# Enregistreur_et_Speaker_Audio.net
KiCad netlist of a schematic drawn in Altium Designer
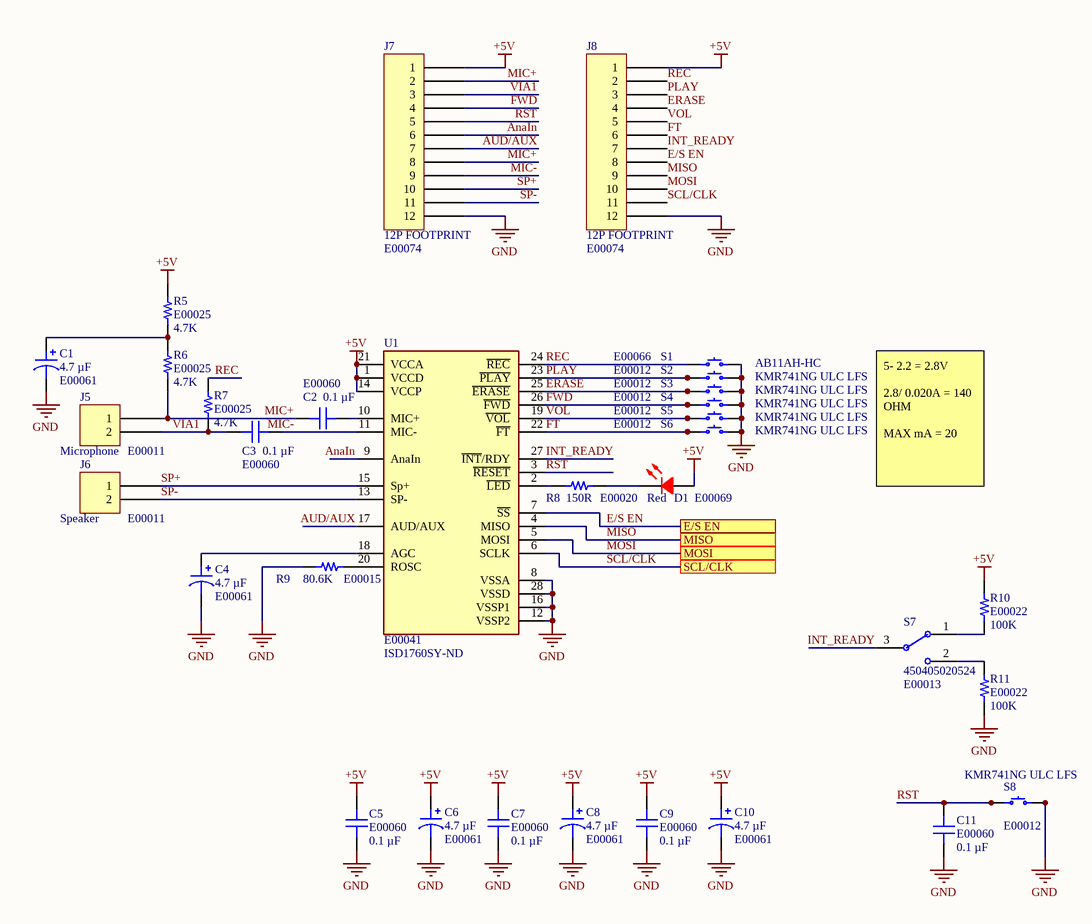
[diagram p0: Enregistreur et Speaker Audio.SchDoc]

(export (version "E")
  (design (tool "Eeschema 10.0.6"))
  (components
    (comp (ref "C1")
      (value "4.7 µF")
      (footprint "CAP ALUM 4.3MM2")
      (description "CAP ALUM 4.7UF 20% 35V SMD")
      (fields
        (field (name "MANUFACTURER") "United Chemi-Con")
        (field (name "TOLERANCE") "±20%")
        (field (name "ADAM INVENTORY NUMBER 1") "E00061")
      )
      (libsource (lib "ADAM LIBRARY") (part "CAP ALUM 4.7UF 20% 35V"))
    )
    (comp (ref "C2")
      (value "0.1 µF")
      (footprint "CAP 0603")
      (description "CAP CER 0.1UF 50V X7R 0603")
      (fields
        (field (name "MANUFACTURER") "KEMET")
        (field (name "TOLERANCE") "±10%")
        (field (name "ADAM INVENTORY NUMBER 1") "E00060")
      )
      (libsource (lib "ADAM LIBRARY") (part "CAP CER 0.1UF 50V X7R 0603"))
    )
    (comp (ref "C3")
      (value "0.1 µF")
      (footprint "CAP 0603")
      (description "CAP CER 0.1UF 50V X7R 0603")
      (fields
        (field (name "MANUFACTURER") "KEMET")
        (field (name "TOLERANCE") "±10%")
        (field (name "ADAM INVENTORY NUMBER 1") "E00060")
      )
      (libsource (lib "ADAM LIBRARY") (part "CAP CER 0.1UF 50V X7R 0603"))
    )
    (comp (ref "C4")
      (value "4.7 µF")
      (footprint "CAP ALUM 4.3MM2")
      (description "CAP ALUM 4.7UF 20% 35V SMD")
      (fields
        (field (name "MANUFACTURER") "United Chemi-Con")
        (field (name "TOLERANCE") "±20%")
        (field (name "ADAM INVENTORY NUMBER 1") "E00061")
      )
      (libsource (lib "ADAM LIBRARY") (part "CAP ALUM 4.7UF 20% 35V"))
    )
    (comp (ref "C5")
      (value "0.1 µF")
      (footprint "CAP 0603")
      (description "CAP CER 0.1UF 50V X7R 0603")
      (fields
        (field (name "MANUFACTURER") "KEMET")
        (field (name "TOLERANCE") "±10%")
        (field (name "ADAM INVENTORY NUMBER 1") "E00060")
      )
      (libsource (lib "ADAM LIBRARY") (part "CAP CER 0.1UF 50V X7R 0603"))
    )
    (comp (ref "C6")
      (value "4.7 µF")
      (footprint "CAP ALUM 4.3MM2")
      (description "CAP ALUM 4.7UF 20% 35V SMD")
      (fields
        (field (name "MANUFACTURER") "United Chemi-Con")
        (field (name "TOLERANCE") "±20%")
        (field (name "ADAM INVENTORY NUMBER 1") "E00061")
      )
      (libsource (lib "ADAM LIBRARY") (part "CAP ALUM 4.7UF 20% 35V"))
    )
    (comp (ref "C7")
      (value "0.1 µF")
      (footprint "CAP 0603")
      (description "CAP CER 0.1UF 50V X7R 0603")
      (fields
        (field (name "MANUFACTURER") "KEMET")
        (field (name "TOLERANCE") "±10%")
        (field (name "ADAM INVENTORY NUMBER 1") "E00060")
      )
      (libsource (lib "ADAM LIBRARY") (part "CAP CER 0.1UF 50V X7R 0603"))
    )
    (comp (ref "C8")
      (value "4.7 µF")
      (footprint "CAP ALUM 4.3MM2")
      (description "CAP ALUM 4.7UF 20% 35V SMD")
      (fields
        (field (name "MANUFACTURER") "United Chemi-Con")
        (field (name "TOLERANCE") "±20%")
        (field (name "ADAM INVENTORY NUMBER 1") "E00061")
      )
      (libsource (lib "ADAM LIBRARY") (part "CAP ALUM 4.7UF 20% 35V"))
    )
    (comp (ref "C9")
      (value "0.1 µF")
      (footprint "CAP 0603")
      (description "CAP CER 0.1UF 50V X7R 0603")
      (fields
        (field (name "MANUFACTURER") "KEMET")
        (field (name "TOLERANCE") "±10%")
        (field (name "ADAM INVENTORY NUMBER 1") "E00060")
      )
      (libsource (lib "ADAM LIBRARY") (part "CAP CER 0.1UF 50V X7R 0603"))
    )
    (comp (ref "C10")
      (value "4.7 µF")
      (footprint "CAP ALUM 4.3MM2")
      (description "CAP ALUM 4.7UF 20% 35V SMD")
      (fields
        (field (name "MANUFACTURER") "United Chemi-Con")
        (field (name "TOLERANCE") "±20%")
        (field (name "ADAM INVENTORY NUMBER 1") "E00061")
      )
      (libsource (lib "ADAM LIBRARY") (part "CAP ALUM 4.7UF 20% 35V"))
    )
    (comp (ref "C11")
      (value "0.1 µF")
      (footprint "CAP 0603")
      (description "CAP CER 0.1UF 50V X7R 0603")
      (fields
        (field (name "MANUFACTURER") "KEMET")
        (field (name "TOLERANCE") "±10%")
        (field (name "ADAM INVENTORY NUMBER 1") "E00060")
      )
      (libsource (lib "ADAM LIBRARY") (part "CAP CER 0.1UF 50V X7R 0603"))
    )
    (comp (ref "D1")
      (value "Red")
      (footprint "Red Led 0603")
      (description "0603 RED LED")
      (fields
        (field (name "MANUFACTURER") "American Bright Optoelectronics Corporation")
        (field (name "ADAM INVENTORY NUMBER 1") "E00069")
      )
      (libsource (lib "ADAM LIBRARY") (part "0603 RED LED"))
    )
    (comp (ref "J5")
      (value "Microphone")
      (footprint "TERM BLOC 2P")
      (description "TERM BLK 2P SIDE ENT 2.54MM PCB")
      (fields
        (field (name "MANUFACTURER") "TE Connectivity AMP Connectors")
        (field (name "VOLTAGE") "150V")
        (field (name "ADAM INVENTORY NUMBER 1") "E00011")
      )
      (libsource (lib "ADAM LIBRARY") (part "TERM BLK 2P SIDE ENT 2.54MM PCB"))
    )
    (comp (ref "J6")
      (value "Speaker")
      (footprint "TERM BLOC 2P")
      (description "TERM BLK 2P SIDE ENT 2.54MM PCB")
      (fields
        (field (name "MANUFACTURER") "TE Connectivity AMP Connectors")
        (field (name "VOLTAGE") "150V")
        (field (name "ADAM INVENTORY NUMBER 1") "E00011")
      )
      (libsource (lib "ADAM LIBRARY") (part "TERM BLK 2P SIDE ENT 2.54MM PCB"))
    )
    (comp (ref "J7")
      (value "12P FOOTPRINT")
      (footprint "CONN 12PIN FEMALE")
      (description "FOOTPRINT FOR TEST OR JUST IN CASE")
      (fields (field (name "MANUFACTURER") "Harwin Inc.") (field (name "ADAM INVENTORY NUMBER 1") "E00074"))
      (libsource (lib "ADAM LIBRARY") (part "12P FOOTPRINT"))
    )
    (comp (ref "J8")
      (value "12P FOOTPRINT")
      (footprint "CONN 12PIN FEMALE")
      (description "FOOTPRINT FOR TEST OR JUST IN CASE")
      (fields (field (name "MANUFACTURER") "Harwin Inc.") (field (name "ADAM INVENTORY NUMBER 1") "E00074"))
      (libsource (lib "ADAM LIBRARY") (part "12P FOOTPRINT"))
    )
    (comp (ref "R5")
      (value "4.7K")
      (footprint "RES 0603")
      (description "RES 4.7K OHM 1% 1/10W 0603")
      (fields
        (field (name "MANUFACTURER") "Stackpole Electronics Inc")
        (field (name "TOLERANCE") "±1%")
        (field (name "ADAM INVENTORY NUMBER 1") "E00025")
      )
      (libsource (lib "ADAM LIBRARY") (part "RES SMD 4.7K OHM"))
    )
    (comp (ref "R6")
      (value "4.7K")
      (footprint "RES 0603")
      (description "RES 4.7K OHM 1% 1/10W 0603")
      (fields
        (field (name "MANUFACTURER") "Stackpole Electronics Inc")
        (field (name "TOLERANCE") "±1%")
        (field (name "ADAM INVENTORY NUMBER 1") "E00025")
      )
      (libsource (lib "ADAM LIBRARY") (part "RES SMD 4.7K OHM"))
    )
    (comp (ref "R7")
      (value "4.7K")
      (footprint "RES 0603")
      (description "RES 4.7K OHM 1% 1/10W 0603")
      (fields
        (field (name "MANUFACTURER") "Stackpole Electronics Inc")
        (field (name "TOLERANCE") "±1%")
        (field (name "ADAM INVENTORY NUMBER 1") "E00025")
      )
      (libsource (lib "ADAM LIBRARY") (part "RES SMD 4.7K OHM"))
    )
    (comp (ref "R8")
      (value "150R")
      (footprint "RES 0603")
      (description "RES SMD 150 OHM 0.1% 1/8W 0603")
      (fields
        (field (name "MANUFACTURER") "Vishay Beyschlag")
        (field (name "TOLERANCE") "±0.1%")
        (field (name "ADAM INVENTORY NUMBER 1") "E00020")
      )
      (libsource (lib "ADAM LIBRARY") (part "RES SMD 150 OHM"))
    )
    (comp (ref "R9")
      (value "80.6K")
      (footprint "RES 0603")
      (description "RES SMD 80.6K OHM 1% 1/4W 0603")
      (fields
        (field (name "MANUFACTURER") "Vishay Dale")
        (field (name "TOLERANCE") "±1%")
        (field (name "ADAM INVENTORY NUMBER 1") "E00015")
      )
      (libsource (lib "ADAM LIBRARY") (part "RES SMD 80.6K OHM"))
    )
    (comp (ref "R10")
      (value "100K")
      (footprint "RES 0603")
      (description "RES SMD 100K OHM 1% 1/4W 0603")
      (fields
        (field (name "MANUFACTURER") "Vishay Dale")
        (field (name "TOLERANCE") "±1%")
        (field (name "ADAM INVENTORY NUMBER 1") "E00022")
      )
      (libsource (lib "ADAM LIBRARY") (part "RES SMD 100K OHM"))
    )
    (comp (ref "R11")
      (value "100K")
      (footprint "RES 0603")
      (description "RES SMD 100K OHM 1% 1/4W 0603")
      (fields
        (field (name "MANUFACTURER") "Vishay Dale")
        (field (name "TOLERANCE") "±1%")
        (field (name "ADAM INVENTORY NUMBER 1") "E00022")
      )
      (libsource (lib "ADAM LIBRARY") (part "RES SMD 100K OHM"))
    )
    (comp (ref "S1")
      (value "AB11AH-HC")
      (footprint "BUTTON AB11AH-HC")
      (description "SWITCH PUSH SPST-NO 0.4VA 28V")
      (fields (field (name "MANUFACTURER") "NKK Switches") (field (name "ADAM INVENTORY NUMBER 1") "E00066"))
      (libsource (lib "ADAM LIBRARY") (part "AB11AH-HC"))
    )
    (comp (ref "S2")
      (value "KMR741NG ULC LFS")
      (footprint "Switch Lin SMD")
      (description "SWITCH TACTILE SPST-NO 50MA 32V")
      (fields (field (name "MANUFACTURER") "C&K") (field (name "ADAM INVENTORY NUMBER 1") "E00012"))
      (libsource (lib "ADAM LIBRARY") (part "Sw Lin"))
    )
    (comp (ref "S3")
      (value "KMR741NG ULC LFS")
      (footprint "Switch Lin SMD")
      (description "SWITCH TACTILE SPST-NO 50MA 32V")
      (fields (field (name "MANUFACTURER") "C&K") (field (name "ADAM INVENTORY NUMBER 1") "E00012"))
      (libsource (lib "ADAM LIBRARY") (part "Sw Lin"))
    )
    (comp (ref "S4")
      (value "KMR741NG ULC LFS")
      (footprint "Switch Lin SMD")
      (description "SWITCH TACTILE SPST-NO 50MA 32V")
      (fields (field (name "MANUFACTURER") "C&K") (field (name "ADAM INVENTORY NUMBER 1") "E00012"))
      (libsource (lib "ADAM LIBRARY") (part "Sw Lin"))
    )
    (comp (ref "S5")
      (value "KMR741NG ULC LFS")
      (footprint "Switch Lin SMD")
      (description "SWITCH TACTILE SPST-NO 50MA 32V")
      (fields (field (name "MANUFACTURER") "C&K") (field (name "ADAM INVENTORY NUMBER 1") "E00012"))
      (libsource (lib "ADAM LIBRARY") (part "Sw Lin"))
    )
    (comp (ref "S6")
      (value "KMR741NG ULC LFS")
      (footprint "Switch Lin SMD")
      (description "SWITCH TACTILE SPST-NO 50MA 32V")
      (fields (field (name "MANUFACTURER") "C&K") (field (name "ADAM INVENTORY NUMBER 1") "E00012"))
      (libsource (lib "ADAM LIBRARY") (part "Sw Lin"))
    )
    (comp (ref "S7")
      (value "450405020524")
      (footprint "SL 3Pos Switch")
      (description "SMT 8.7 X 3.0 MM MINI SLIDE SWIT")
      (fields
        (field (name "MANUFACTURER") "Würth Elektronik")
        (field (name "ADAM INVENTORY NUMBER 1") "E00013")
        (field (name "PUBLISHER") "Wurth Elektronik")
      )
      (libsource (lib "ADAM LIBRARY") (part "SLIDE SWIT"))
    )
    (comp (ref "S8")
      (value "KMR741NG ULC LFS")
      (footprint "Switch Lin SMD")
      (description "SWITCH TACTILE SPST-NO 50MA 32V")
      (fields (field (name "MANUFACTURER") "C&K") (field (name "ADAM INVENTORY NUMBER 1") "E00012"))
      (libsource (lib "ADAM LIBRARY") (part "Sw Lin"))
    )
    (comp (ref "U1")
      (value "ISD1760SY")
      (footprint "ISD1760SY")
      (description "Voice Record/Playback IC Multiple Message 40 ~ 120 Sec Pushbutton, SPI 28-SOIC")
      (fields
        (field (name "ADAM INVENTORY NUMBER 1") "E00041")
        (field (name "SUPPLIER PART NUMBER 1") "ISD1760SY-ND")
      )
      (libsource (lib "ADAM LIBRARY") (part "ISD1760SY"))
    )
  )
  (nets
    (net (code "1") (name "+5V") (class "Default")
      (node (ref "C10") (pin "1") (pinfunction "1_1") (pintype "passive"))
      (node (ref "C5") (pin "2") (pinfunction "2_2") (pintype "passive"))
      (node (ref "C6") (pin "1") (pinfunction "1_1") (pintype "passive"))
      (node (ref "C7") (pin "2") (pinfunction "2_2") (pintype "passive"))
      (node (ref "C8") (pin "1") (pinfunction "1_1") (pintype "passive"))
      (node (ref "C9") (pin "2") (pinfunction "2_2") (pintype "passive"))
      (node (ref "D1") (pin "1") (pinfunction "1_1") (pintype "passive"))
      (node (ref "J7") (pin "1") (pinfunction "1_1") (pintype "passive"))
      (node (ref "J8") (pin "1") (pinfunction "1_1") (pintype "passive"))
      (node (ref "R10") (pin "2") (pinfunction "2_2") (pintype "passive"))
      (node (ref "R5") (pin "2") (pinfunction "2_2") (pintype "passive"))
      (node (ref "U1") (pin "1") (pinfunction "VCCD_1") (pintype "passive"))
      (node (ref "U1") (pin "14") (pinfunction "VCCP_14") (pintype "passive"))
      (node (ref "U1") (pin "21") (pinfunction "VCCA_21") (pintype "passive"))
    )
    (net (code "2") (name "/AUD{slash}AUX") (class "Default")
      (node (ref "J7") (pin "7") (pinfunction "7_7") (pintype "passive"))
      (node (ref "U1") (pin "17") (pinfunction "AUD/AUX_17") (pintype "passive"))
    )
    (net (code "3") (name "/AnaIn") (class "Default")
      (node (ref "J7") (pin "6") (pinfunction "6_6") (pintype "passive"))
      (node (ref "U1") (pin "9") (pinfunction "AnaIn_9") (pintype "passive"))
    )
    (net (code "4") (name "/ERASE") (class "Default")
      (node (ref "J8") (pin "4") (pinfunction "4_4") (pintype "passive"))
      (node (ref "S3") (pin "1") (pinfunction "1_1") (pintype "passive"))
      (node (ref "S3") (pin "2") (pinfunction "2_2") (pintype "passive"))
      (node (ref "U1") (pin "25") (pinfunction "~{ERASE}_25") (pintype "passive"))
    )
    (net (code "5") (name "/E{slash}S EN") (class "Default")
      (node (ref "J8") (pin "8") (pinfunction "8_8") (pintype "passive"))
      (node (ref "U1") (pin "7") (pinfunction "~{SS}_7") (pintype "passive"))
    )
    (net (code "6") (name "/FT") (class "Default")
      (node (ref "J8") (pin "6") (pinfunction "6_6") (pintype "passive"))
      (node (ref "S6") (pin "1") (pinfunction "1_1") (pintype "passive"))
      (node (ref "S6") (pin "2") (pinfunction "2_2") (pintype "passive"))
      (node (ref "U1") (pin "22") (pinfunction "~{FT}_22") (pintype "passive"))
    )
    (net (code "7") (name "/FWD") (class "Default")
      (node (ref "J7") (pin "4") (pinfunction "4_4") (pintype "passive"))
      (node (ref "S4") (pin "1") (pinfunction "1_1") (pintype "passive"))
      (node (ref "S4") (pin "2") (pinfunction "2_2") (pintype "passive"))
      (node (ref "U1") (pin "26") (pinfunction "~{FWD}_26") (pintype "passive"))
    )
    (net (code "8") (name "/INT_READY") (class "Default")
      (node (ref "J8") (pin "7") (pinfunction "7_7") (pintype "passive"))
      (node (ref "S7") (pin "3") (pinfunction "COM_3") (pintype "passive"))
      (node (ref "U1") (pin "27") (pinfunction "~{INT}/RDY_27") (pintype "passive"))
    )
    (net (code "9") (name "/MIC+") (class "Default")
      (node (ref "C2") (pin "2") (pinfunction "2_2") (pintype "passive"))
      (node (ref "J5") (pin "1") (pinfunction "1_1") (pintype "passive"))
      (node (ref "J7") (pin "2") (pinfunction "2_2") (pintype "passive"))
      (node (ref "J7") (pin "8") (pinfunction "8_8") (pintype "passive"))
      (node (ref "R6") (pin "1") (pinfunction "1_1") (pintype "passive"))
    )
    (net (code "10") (name "/MIC-") (class "Default")
      (node (ref "C3") (pin "1") (pinfunction "1_1") (pintype "passive"))
      (node (ref "J7") (pin "9") (pinfunction "9_9") (pintype "passive"))
      (node (ref "U1") (pin "11") (pinfunction "MIC-_11") (pintype "passive"))
    )
    (net (code "11") (name "/MISO") (class "Default")
      (node (ref "J8") (pin "9") (pinfunction "9_9") (pintype "passive"))
      (node (ref "U1") (pin "4") (pinfunction "MISO_4") (pintype "passive"))
    )
    (net (code "12") (name "/MOSI") (class "Default")
      (node (ref "J8") (pin "10") (pinfunction "10_10") (pintype "passive"))
      (node (ref "U1") (pin "5") (pinfunction "MOSI_5") (pintype "passive"))
    )
    (net (code "13") (name "/PLAY") (class "Default")
      (node (ref "J8") (pin "3") (pinfunction "3_3") (pintype "passive"))
      (node (ref "S2") (pin "1") (pinfunction "1_1") (pintype "passive"))
      (node (ref "S2") (pin "2") (pinfunction "2_2") (pintype "passive"))
      (node (ref "U1") (pin "23") (pinfunction "~{PLAY}_23") (pintype "passive"))
    )
    (net (code "14") (name "/REC") (class "Default")
      (node (ref "J8") (pin "2") (pinfunction "2_2") (pintype "passive"))
      (node (ref "R7") (pin "2") (pinfunction "2_2") (pintype "passive"))
      (node (ref "S1") (pin "1") (pinfunction "1_1") (pintype "passive"))
      (node (ref "U1") (pin "24") (pinfunction "~{REC}_24") (pintype "passive"))
    )
    (net (code "15") (name "/RST") (class "Default")
      (node (ref "C11") (pin "2") (pinfunction "2_2") (pintype "passive"))
      (node (ref "J7") (pin "5") (pinfunction "5_5") (pintype "passive"))
      (node (ref "S8") (pin "1") (pinfunction "1_1") (pintype "passive"))
      (node (ref "S8") (pin "2") (pinfunction "2_2") (pintype "passive"))
      (node (ref "U1") (pin "3") (pinfunction "~{RESET}_3") (pintype "passive"))
    )
    (net (code "16") (name "/SCL{slash}CLK") (class "Default")
      (node (ref "J8") (pin "11") (pinfunction "11_11") (pintype "passive"))
      (node (ref "U1") (pin "6") (pinfunction "SCLK_6") (pintype "passive"))
    )
    (net (code "17") (name "/SP+") (class "Default")
      (node (ref "J6") (pin "1") (pinfunction "1_1") (pintype "passive"))
      (node (ref "J7") (pin "10") (pinfunction "10_10") (pintype "passive"))
      (node (ref "U1") (pin "15") (pinfunction "Sp+_15") (pintype "passive"))
    )
    (net (code "18") (name "/SP-") (class "Default")
      (node (ref "J6") (pin "2") (pinfunction "2_2") (pintype "passive"))
      (node (ref "J7") (pin "11") (pinfunction "11_11") (pintype "passive"))
      (node (ref "U1") (pin "13") (pinfunction "SP-_13") (pintype "passive"))
    )
    (net (code "19") (name "/VIA1") (class "Default")
      (node (ref "C3") (pin "2") (pinfunction "2_2") (pintype "passive"))
      (node (ref "J5") (pin "2") (pinfunction "2_2") (pintype "passive"))
      (node (ref "J7") (pin "3") (pinfunction "3_3") (pintype "passive"))
      (node (ref "R7") (pin "1") (pinfunction "1_1") (pintype "passive"))
    )
    (net (code "20") (name "/VOL") (class "Default")
      (node (ref "J8") (pin "5") (pinfunction "5_5") (pintype "passive"))
      (node (ref "S5") (pin "1") (pinfunction "1_1") (pintype "passive"))
      (node (ref "S5") (pin "2") (pinfunction "2_2") (pintype "passive"))
      (node (ref "U1") (pin "19") (pinfunction "~{VOL}_19") (pintype "passive"))
    )
    (net (code "21") (name "GND") (class "Default")
      (node (ref "C1") (pin "2") (pinfunction "2_2") (pintype "passive"))
      (node (ref "C10") (pin "2") (pinfunction "2_2") (pintype "passive"))
      (node (ref "C11") (pin "1") (pinfunction "1_1") (pintype "passive"))
      (node (ref "C4") (pin "2") (pinfunction "2_2") (pintype "passive"))
      (node (ref "C5") (pin "1") (pinfunction "1_1") (pintype "passive"))
      (node (ref "C6") (pin "2") (pinfunction "2_2") (pintype "passive"))
      (node (ref "C7") (pin "1") (pinfunction "1_1") (pintype "passive"))
      (node (ref "C8") (pin "2") (pinfunction "2_2") (pintype "passive"))
      (node (ref "C9") (pin "1") (pinfunction "1_1") (pintype "passive"))
      (node (ref "J7") (pin "12") (pinfunction "12_12") (pintype "passive"))
      (node (ref "J8") (pin "12") (pinfunction "12_12") (pintype "passive"))
      (node (ref "R11") (pin "1") (pinfunction "1_1") (pintype "passive"))
      (node (ref "R9") (pin "1") (pinfunction "1_1") (pintype "passive"))
      (node (ref "S1") (pin "2") (pinfunction "2_2") (pintype "passive"))
      (node (ref "S2") (pin "3") (pinfunction "3_3") (pintype "passive"))
      (node (ref "S2") (pin "4") (pinfunction "4_4") (pintype "passive"))
      (node (ref "S3") (pin "3") (pinfunction "3_3") (pintype "passive"))
      (node (ref "S3") (pin "4") (pinfunction "4_4") (pintype "passive"))
      (node (ref "S4") (pin "3") (pinfunction "3_3") (pintype "passive"))
      (node (ref "S4") (pin "4") (pinfunction "4_4") (pintype "passive"))
      (node (ref "S5") (pin "3") (pinfunction "3_3") (pintype "passive"))
      (node (ref "S5") (pin "4") (pinfunction "4_4") (pintype "passive"))
      (node (ref "S6") (pin "3") (pinfunction "3_3") (pintype "passive"))
      (node (ref "S6") (pin "4") (pinfunction "4_4") (pintype "passive"))
      (node (ref "S8") (pin "3") (pinfunction "3_3") (pintype "passive"))
      (node (ref "S8") (pin "4") (pinfunction "4_4") (pintype "passive"))
      (node (ref "U1") (pin "12") (pinfunction "VSSP2_12") (pintype "passive"))
      (node (ref "U1") (pin "16") (pinfunction "VSSP1_16") (pintype "passive"))
      (node (ref "U1") (pin "28") (pinfunction "VSSD_28") (pintype "passive"))
      (node (ref "U1") (pin "8") (pinfunction "VSSA_8") (pintype "passive"))
    )
    (net (code "22") (name "Net-(C1-Pad1)") (class "Default")
      (node (ref "C1") (pin "1") (pinfunction "1_1") (pintype "passive"))
      (node (ref "R5") (pin "1") (pinfunction "1_1") (pintype "passive"))
      (node (ref "R6") (pin "2") (pinfunction "2_2") (pintype "passive"))
    )
    (net (code "23") (name "Net-(D1-Pad2)") (class "Default")
      (node (ref "D1") (pin "2") (pinfunction "2_2") (pintype "passive"))
      (node (ref "R8") (pin "2") (pinfunction "2_2") (pintype "passive"))
    )
    (net (code "24") (name "Net-(R10-Pad1)") (class "Default")
      (node (ref "R10") (pin "1") (pinfunction "1_1") (pintype "passive"))
      (node (ref "S7") (pin "1") (pinfunction "1_1") (pintype "passive"))
    )
    (net (code "25") (name "Net-(R11-Pad2)") (class "Default")
      (node (ref "R11") (pin "2") (pinfunction "2_2") (pintype "passive"))
      (node (ref "S7") (pin "2") (pinfunction "2_2") (pintype "passive"))
    )
    (net (code "26") (name "Net-(U1-AGC)") (class "Default")
      (node (ref "C4") (pin "1") (pinfunction "1_1") (pintype "passive"))
      (node (ref "U1") (pin "18") (pinfunction "AGC_18") (pintype "passive"))
    )
    (net (code "27") (name "Net-(U1-MIC+)") (class "Default")
      (node (ref "C2") (pin "1") (pinfunction "1_1") (pintype "passive"))
      (node (ref "U1") (pin "10") (pinfunction "MIC+_10") (pintype "passive"))
    )
    (net (code "28") (name "Net-(U1-ROSC)") (class "Default")
      (node (ref "R9") (pin "2") (pinfunction "2_2") (pintype "passive"))
      (node (ref "U1") (pin "20") (pinfunction "ROSC_20") (pintype "passive"))
    )
    (net (code "29") (name "Net-(U1-~{LED})") (class "Default")
      (node (ref "R8") (pin "1") (pinfunction "1_1") (pintype "passive"))
      (node (ref "U1") (pin "2") (pinfunction "~{LED}_2") (pintype "passive"))
    )
  )
)
